# pcb2.net
KiCad netlist of a schematic drawn in EAGLE
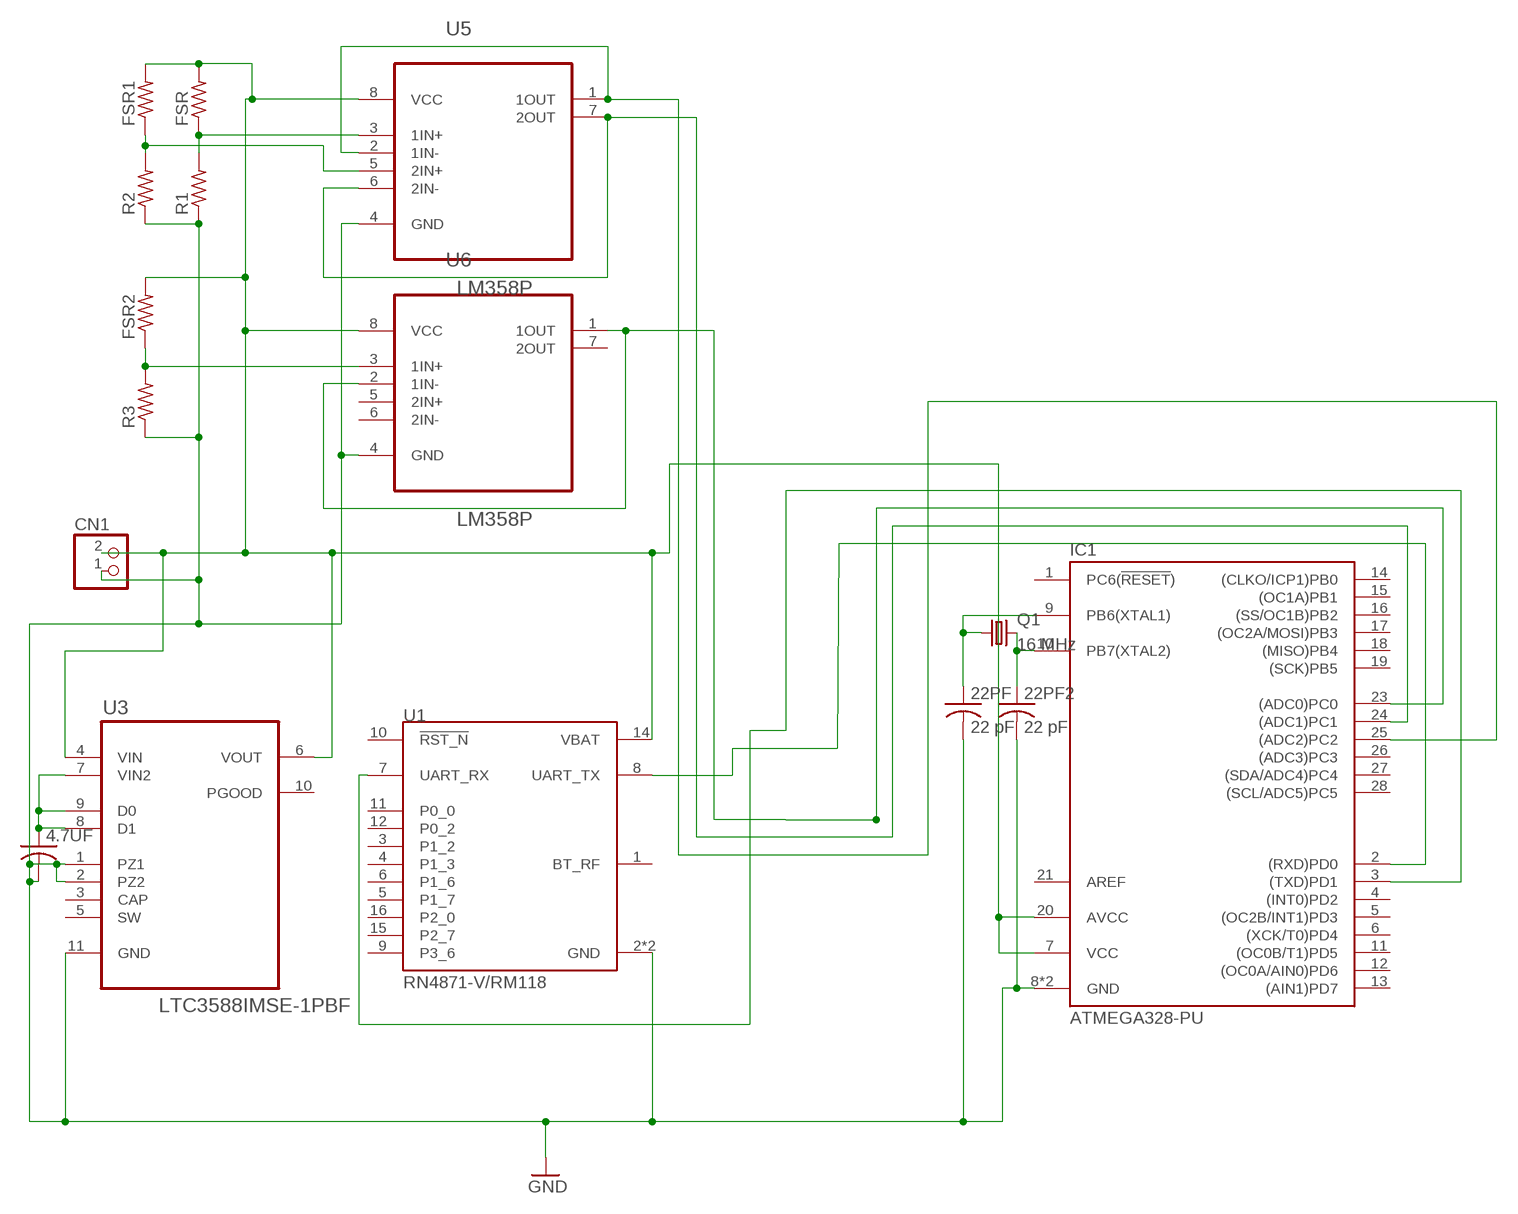
[diagram p0: schematic, sheet 1]

(export (version "E")
  (design (tool "Eeschema 10.0.6"))
  (components
    (comp (ref "4.7UF")
      (value "C-US025-024X044")
      (footprint "eagle-import:C025-024X044")
      (libsource (lib "eagle-import") (part "rcl_334_C-US025-024X044"))
    )
    (comp (ref "22PF")
      (value "22 pF")
      (footprint "eagle-import:C025-024X044")
      (libsource (lib "eagle-import") (part "C-US025-024X044"))
    )
    (comp (ref "22PF2")
      (value "22 pF")
      (footprint "eagle-import:C025-024X044")
      (libsource (lib "eagle-import") (part "C-US025-024X044"))
    )
    (comp (ref "CN1")
      (value "JST_2PIN-THM-RA")
      (footprint "eagle-import:JST-PH-2-THM-RA")
      (libsource (lib "eagle-import") (part "JST_2PIN-THM-RA"))
    )
    (comp (ref "FSR")
      (value "R-US_0204/5")
      (footprint "eagle-import:0204_5")
      (libsource (lib "eagle-import") (part "R-US_0204/5"))
    )
    (comp (ref "FSR1")
      (value "R-US_0204/5")
      (footprint "eagle-import:0204_5")
      (libsource (lib "eagle-import") (part "R-US_0204/5"))
    )
    (comp (ref "FSR2")
      (value "R-US_0204/5")
      (footprint "eagle-import:0204_5")
      (libsource (lib "eagle-import") (part "R-US_0204/5"))
    )
    (comp (ref "IC1")
      (value "ATMEGA328-PU")
      (footprint "eagle-import:DIL28")
      (fields (field (name "MF") "Microchip"))
      (libsource (lib "eagle-import") (part "ATMEGA328-PU"))
    )
    (comp (ref "Q1")
      (value "16 MHz")
      (footprint "eagle-import:HC49U-V")
      (libsource (lib "eagle-import") (part "CRYSTALHC49U-V"))
    )
    (comp (ref "R1")
      (value "R-US_0204/5")
      (footprint "eagle-import:0204_5")
      (libsource (lib "eagle-import") (part "R-US_0204/5"))
    )
    (comp (ref "R2")
      (value "R-US_0204/5")
      (footprint "eagle-import:0204_5")
      (libsource (lib "eagle-import") (part "R-US_0204/5"))
    )
    (comp (ref "R3")
      (value "R-US_0204/5")
      (footprint "eagle-import:0204_5")
      (libsource (lib "eagle-import") (part "R-US_0204/5"))
    )
    (comp (ref "U1")
      (value "RN4871-V/RM118")
      (footprint "eagle-import:XCVR_RN4871-V_RM118")
      (fields (field (name "DIGI-KEY_PART_NUMBER") "RN4871-V/RM118-ND") (field (name "MF") "Microchip"))
      (libsource (lib "eagle-import") (part "RN4871-V/RM118"))
    )
    (comp (ref "U3")
      (value "LTC3588IMSE-1PBF")
      (footprint "eagle-import:SOP50P490X110-11N")
      (fields
        (field (name "DIGI-KEY_PART_NUMBER") "LTC3588IMSE-1#PBF-ND")
        (field (name "MF") "Linear Technology/Analog")
        (field (name "MP") "LTC3588IMSE-1#PBF")
      )
      (libsource (lib "eagle-import") (part "LTC3588IMSE-1PBF"))
    )
    (comp (ref "U5")
      (value "LM358P")
      (footprint "eagle-import:DIP254P762X508-8")
      (fields (field (name "MF") "Texas Instruments"))
      (libsource (lib "eagle-import") (part "LM358P"))
    )
    (comp (ref "U6")
      (value "LM358P")
      (footprint "eagle-import:DIP254P762X508-8")
      (fields (field (name "MF") "Texas Instruments"))
      (libsource (lib "eagle-import") (part "LM358P"))
    )
  )
  (nets
    (net (code "1") (name "GND") (class "Default")
      (node (ref "22PF") (pin "2") (pinfunction "2_2") (pintype "passive"))
      (node (ref "22PF2") (pin "2") (pinfunction "2_2") (pintype "passive"))
      (node (ref "4.7UF") (pin "2") (pinfunction "2_2") (pintype "passive"))
      (node (ref "CN1") (pin "1") (pinfunction "2_1") (pintype "passive"))
      (node (ref "IC1") (pin "22") (pinfunction "GND_22") (pintype "power_in"))
      (node (ref "IC1") (pin "8") (pinfunction "GND_8") (pintype "power_in"))
      (node (ref "R1") (pin "1") (pinfunction "1_1") (pintype "passive"))
      (node (ref "R2") (pin "1") (pinfunction "1_1") (pintype "passive"))
      (node (ref "R3") (pin "1") (pinfunction "1_1") (pintype "passive"))
      (node (ref "U1") (pin "13") (pinfunction "GND_13") (pintype "power_in"))
      (node (ref "U1") (pin "2") (pinfunction "GND_2") (pintype "power_in"))
      (node (ref "U3") (pin "1") (pinfunction "PZ1_1") (pintype "input"))
      (node (ref "U3") (pin "11") (pinfunction "GND_11") (pintype "passive"))
      (node (ref "U3") (pin "2") (pinfunction "PZ2_2") (pintype "input"))
      (node (ref "U5") (pin "4") (pinfunction "GND_4") (pintype "power_in"))
      (node (ref "U6") (pin "4") (pinfunction "GND_4") (pintype "power_in"))
    )
    (net (code "2") (name "Net-(CN1-1)") (class "Default")
      (node (ref "CN1") (pin "2") (pinfunction "1_2") (pintype "passive"))
      (node (ref "FSR") (pin "2") (pinfunction "2_2") (pintype "passive"))
      (node (ref "FSR1") (pin "2") (pinfunction "2_2") (pintype "passive"))
      (node (ref "FSR2") (pin "2") (pinfunction "2_2") (pintype "passive"))
      (node (ref "IC1") (pin "20") (pinfunction "AVCC_20") (pintype "power_in"))
      (node (ref "IC1") (pin "7") (pinfunction "VCC_7") (pintype "power_in"))
      (node (ref "U1") (pin "14") (pinfunction "VBAT_14") (pintype "power_in"))
      (node (ref "U3") (pin "4") (pinfunction "VIN_4") (pintype "power_in"))
      (node (ref "U3") (pin "6") (pinfunction "VOUT_6") (pintype "output"))
      (node (ref "U5") (pin "8") (pinfunction "VCC_8") (pintype "power_in"))
      (node (ref "U6") (pin "8") (pinfunction "VCC_8") (pintype "power_in"))
    )
    (net (code "3") (name "Net-(IC1-(ADC0)PC0)") (class "Default")
      (node (ref "IC1") (pin "23") (pinfunction "(ADC0)PC0_23") (pintype "bidirectional"))
      (node (ref "U6") (pin "1") (pinfunction "1OUT_1") (pintype "output"))
      (node (ref "U6") (pin "2") (pinfunction "1IN-_2") (pintype "input"))
    )
    (net (code "4") (name "Net-(IC1-(ADC1)PC1)") (class "Default")
      (node (ref "IC1") (pin "24") (pinfunction "(ADC1)PC1_24") (pintype "bidirectional"))
      (node (ref "U5") (pin "6") (pinfunction "2IN-_6") (pintype "input"))
      (node (ref "U5") (pin "7") (pinfunction "2OUT_7") (pintype "output"))
    )
    (net (code "5") (name "Net-(IC1-(ADC2)PC2)") (class "Default")
      (node (ref "IC1") (pin "25") (pinfunction "(ADC2)PC2_25") (pintype "bidirectional"))
      (node (ref "U5") (pin "1") (pinfunction "1OUT_1") (pintype "output"))
      (node (ref "U5") (pin "2") (pinfunction "1IN-_2") (pintype "input"))
    )
    (net (code "6") (name "Net-(IC1-(RXD)PD0)") (class "Default")
      (node (ref "IC1") (pin "2") (pinfunction "(RXD)PD0_2") (pintype "bidirectional"))
      (node (ref "U1") (pin "8") (pinfunction "UART_TX_8") (pintype "output"))
    )
    (net (code "7") (name "Net-(IC1-(TXD)PD1)") (class "Default")
      (node (ref "IC1") (pin "3") (pinfunction "(TXD)PD1_3") (pintype "bidirectional"))
      (node (ref "U1") (pin "7") (pinfunction "UART_RX_7") (pintype "input"))
    )
    (net (code "8") (name "Net-(IC1-PB6(XTAL1))") (class "Default")
      (node (ref "22PF") (pin "1") (pinfunction "1_1") (pintype "passive"))
      (node (ref "IC1") (pin "9") (pinfunction "PB6(XTAL1)_9") (pintype "bidirectional"))
      (node (ref "Q1") (pin "1") (pinfunction "1_1") (pintype "passive"))
    )
    (net (code "9") (name "Net-(IC1-PB7(XTAL2))") (class "Default")
      (node (ref "22PF2") (pin "1") (pinfunction "1_1") (pintype "passive"))
      (node (ref "IC1") (pin "10") (pinfunction "PB7(XTAL2)_10") (pintype "bidirectional"))
      (node (ref "Q1") (pin "2") (pinfunction "2_2") (pintype "passive"))
    )
    (net (code "10") (name "Net-(U3-D0)") (class "Default")
      (node (ref "4.7UF") (pin "1") (pinfunction "1_1") (pintype "passive"))
      (node (ref "U3") (pin "7") (pinfunction "VIN2_7") (pintype "power_in"))
      (node (ref "U3") (pin "8") (pinfunction "D1_8") (pintype "input"))
      (node (ref "U3") (pin "9") (pinfunction "D0_9") (pintype "input"))
    )
    (net (code "11") (name "Net-(U5-1IN+)") (class "Default")
      (node (ref "FSR") (pin "1") (pinfunction "1_1") (pintype "passive"))
      (node (ref "R1") (pin "2") (pinfunction "2_2") (pintype "passive"))
      (node (ref "U5") (pin "3") (pinfunction "1IN+_3") (pintype "input"))
    )
    (net (code "12") (name "Net-(U5-2IN+)") (class "Default")
      (node (ref "FSR1") (pin "1") (pinfunction "1_1") (pintype "passive"))
      (node (ref "R2") (pin "2") (pinfunction "2_2") (pintype "passive"))
      (node (ref "U5") (pin "5") (pinfunction "2IN+_5") (pintype "input"))
    )
    (net (code "13") (name "Net-(U6-1IN+)") (class "Default")
      (node (ref "FSR2") (pin "1") (pinfunction "1_1") (pintype "passive"))
      (node (ref "R3") (pin "2") (pinfunction "2_2") (pintype "passive"))
      (node (ref "U6") (pin "3") (pinfunction "1IN+_3") (pintype "input"))
    )
    (net (code "14") (name "unconnected-(IC1-(ADC3)PC3-Pad26)") (class "Default")
      (node (ref "IC1") (pin "26") (pinfunction "(ADC3)PC3_26") (pintype "bidirectional"))
    )
    (net (code "15") (name "unconnected-(IC1-(AIN1)PD7-Pad13)") (class "Default")
      (node (ref "IC1") (pin "13") (pinfunction "(AIN1)PD7_13") (pintype "bidirectional"))
    )
    (net (code "16") (name "unconnected-(IC1-(CLKO{slash}ICP1)PB0-Pad14)") (class "Default")
      (node (ref "IC1") (pin "14") (pinfunction "(CLKO/ICP1)PB0_14") (pintype "bidirectional"))
    )
    (net (code "17") (name "unconnected-(IC1-(INT0)PD2-Pad4)") (class "Default")
      (node (ref "IC1") (pin "4") (pinfunction "(INT0)PD2_4") (pintype "bidirectional"))
    )
    (net (code "18") (name "unconnected-(IC1-(MISO)PB4-Pad18)") (class "Default")
      (node (ref "IC1") (pin "18") (pinfunction "(MISO)PB4_18") (pintype "bidirectional"))
    )
    (net (code "19") (name "unconnected-(IC1-(OC0A{slash}AIN0)PD6-Pad12)") (class "Default")
      (node (ref "IC1") (pin "12") (pinfunction "(OC0A/AIN0)PD6_12") (pintype "bidirectional"))
    )
    (net (code "20") (name "unconnected-(IC1-(OC0B{slash}T1)PD5-Pad11)") (class "Default")
      (node (ref "IC1") (pin "11") (pinfunction "(OC0B/T1)PD5_11") (pintype "bidirectional"))
    )
    (net (code "21") (name "unconnected-(IC1-(OC1A)PB1-Pad15)") (class "Default")
      (node (ref "IC1") (pin "15") (pinfunction "(OC1A)PB1_15") (pintype "bidirectional"))
    )
    (net (code "22") (name "unconnected-(IC1-(OC2A{slash}MOSI)PB3-Pad17)") (class "Default")
      (node (ref "IC1") (pin "17") (pinfunction "(OC2A/MOSI)PB3_17") (pintype "bidirectional"))
    )
    (net (code "23") (name "unconnected-(IC1-(OC2B{slash}INT1)PD3-Pad5)") (class "Default")
      (node (ref "IC1") (pin "5") (pinfunction "(OC2B/INT1)PD3_5") (pintype "bidirectional"))
    )
    (net (code "24") (name "unconnected-(IC1-(SCK)PB5-Pad19)") (class "Default")
      (node (ref "IC1") (pin "19") (pinfunction "(SCK)PB5_19") (pintype "bidirectional"))
    )
    (net (code "25") (name "unconnected-(IC1-(SCL{slash}ADC5)PC5-Pad28)") (class "Default")
      (node (ref "IC1") (pin "28") (pinfunction "(SCL/ADC5)PC5_28") (pintype "bidirectional"))
    )
    (net (code "26") (name "unconnected-(IC1-(SDA{slash}ADC4)PC4-Pad27)") (class "Default")
      (node (ref "IC1") (pin "27") (pinfunction "(SDA/ADC4)PC4_27") (pintype "bidirectional"))
    )
    (net (code "27") (name "unconnected-(IC1-(SS{slash}OC1B)PB2-Pad16)") (class "Default")
      (node (ref "IC1") (pin "16") (pinfunction "(SS/OC1B)PB2_16") (pintype "bidirectional"))
    )
    (net (code "28") (name "unconnected-(IC1-(XCK{slash}T0)PD4-Pad6)") (class "Default")
      (node (ref "IC1") (pin "6") (pinfunction "(XCK/T0)PD4_6") (pintype "bidirectional"))
    )
    (net (code "29") (name "unconnected-(IC1-AREF-Pad21)") (class "Default")
      (node (ref "IC1") (pin "21") (pinfunction "AREF_21") (pintype "passive"))
    )
    (net (code "30") (name "unconnected-(IC1-PC6(~{RESET})-Pad1)") (class "Default")
      (node (ref "IC1") (pin "1") (pinfunction "PC6(~{RESET})_1") (pintype "bidirectional"))
    )
    (net (code "31") (name "unconnected-(U1-BT_RF-Pad1)") (class "Default")
      (node (ref "U1") (pin "1") (pinfunction "BT_RF_1") (pintype "bidirectional"))
    )
    (net (code "32") (name "unconnected-(U1-P0_0-Pad11)") (class "Default")
      (node (ref "U1") (pin "11") (pinfunction "P0_0_11") (pintype "bidirectional"))
    )
    (net (code "33") (name "unconnected-(U1-P0_2-Pad12)") (class "Default")
      (node (ref "U1") (pin "12") (pinfunction "P0_2_12") (pintype "bidirectional"))
    )
    (net (code "34") (name "unconnected-(U1-P1_2-Pad3)") (class "Default")
      (node (ref "U1") (pin "3") (pinfunction "P1_2_3") (pintype "bidirectional"))
    )
    (net (code "35") (name "unconnected-(U1-P1_3-Pad4)") (class "Default")
      (node (ref "U1") (pin "4") (pinfunction "P1_3_4") (pintype "bidirectional"))
    )
    (net (code "36") (name "unconnected-(U1-P1_6-Pad6)") (class "Default")
      (node (ref "U1") (pin "6") (pinfunction "P1_6_6") (pintype "bidirectional"))
    )
    (net (code "37") (name "unconnected-(U1-P1_7-Pad5)") (class "Default")
      (node (ref "U1") (pin "5") (pinfunction "P1_7_5") (pintype "bidirectional"))
    )
    (net (code "38") (name "unconnected-(U1-P2_0-Pad16)") (class "Default")
      (node (ref "U1") (pin "16") (pinfunction "P2_0_16") (pintype "bidirectional"))
    )
    (net (code "39") (name "unconnected-(U1-P2_7-Pad15)") (class "Default")
      (node (ref "U1") (pin "15") (pinfunction "P2_7_15") (pintype "bidirectional"))
    )
    (net (code "40") (name "unconnected-(U1-P3_6-Pad9)") (class "Default")
      (node (ref "U1") (pin "9") (pinfunction "P3_6_9") (pintype "bidirectional"))
    )
    (net (code "41") (name "unconnected-(U1-~{RST_N}-Pad10)") (class "Default")
      (node (ref "U1") (pin "10") (pinfunction "~{RST_N}_10") (pintype "input"))
    )
    (net (code "42") (name "unconnected-(U3-CAP-Pad3)") (class "Default")
      (node (ref "U3") (pin "3") (pinfunction "CAP_3") (pintype "passive"))
    )
    (net (code "43") (name "unconnected-(U3-PGOOD-Pad10)") (class "Default")
      (node (ref "U3") (pin "10") (pinfunction "PGOOD_10") (pintype "output"))
    )
    (net (code "44") (name "unconnected-(U3-SW-Pad5)") (class "Default")
      (node (ref "U3") (pin "5") (pinfunction "SW_5") (pintype "passive"))
    )
    (net (code "45") (name "unconnected-(U6-2IN+-Pad5)") (class "Default")
      (node (ref "U6") (pin "5") (pinfunction "2IN+_5") (pintype "input"))
    )
    (net (code "46") (name "unconnected-(U6-2IN--Pad6)") (class "Default")
      (node (ref "U6") (pin "6") (pinfunction "2IN-_6") (pintype "input"))
    )
    (net (code "47") (name "unconnected-(U6-2OUT-Pad7)") (class "Default")
      (node (ref "U6") (pin "7") (pinfunction "2OUT_7") (pintype "output"))
    )
  )
)
